# test.net
KiCad netlist of a schematic drawn in EAGLE
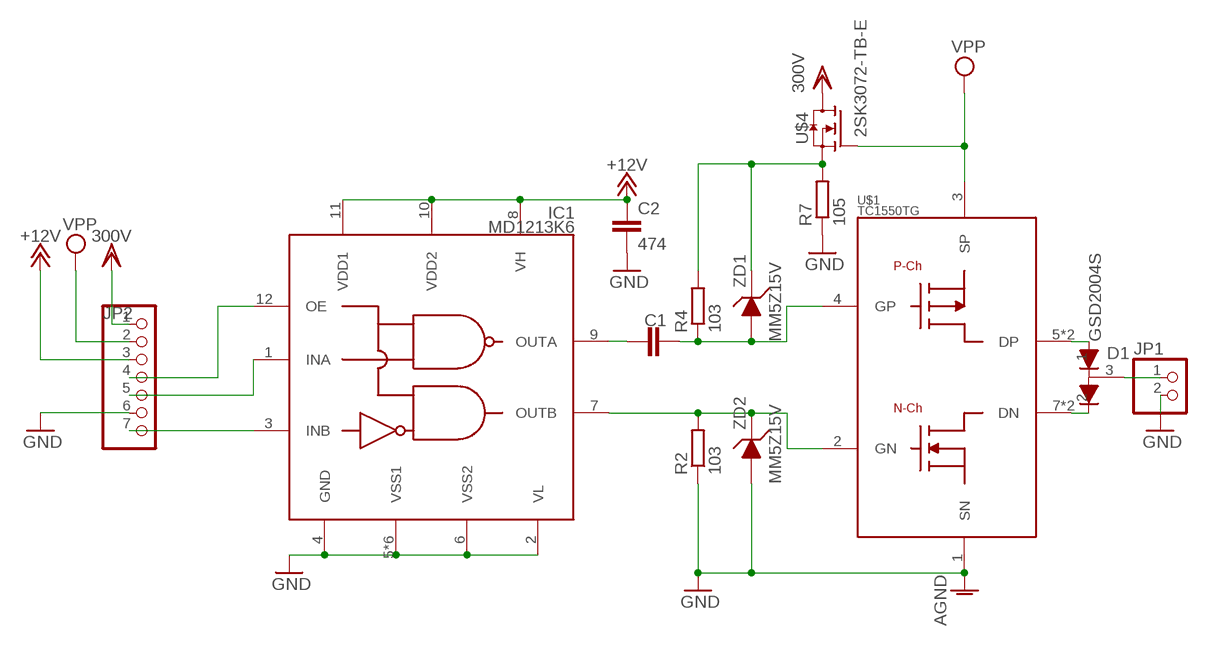
[diagram p0: schematic, sheet 1]

(export (version "E")
  (design (tool "Eeschema 10.0.6"))
  (components
    (comp (ref "C1")
      (value "C-EUC3216")
      (footprint "eagle-import:C3216")
      (libsource (lib "eagle-import") (part "C-EUC3216"))
    )
    (comp (ref "C2")
      (value "474")
      (footprint "eagle-import:C025-024X044")
      (libsource (lib "eagle-import") (part "C-EU025-024X044"))
    )
    (comp (ref "D1")
      (value "GSD2004S")
      (footprint "eagle-import:SOT23")
      (libsource (lib "eagle-import") (part "GSD2004S"))
    )
    (comp (ref "IC1")
      (value "MD1213K6")
      (footprint "eagle-import:QFN12")
      (libsource (lib "eagle-import") (part "MD1213K6"))
    )
    (comp (ref "JP1")
      (value "PINHD-1X2")
      (footprint "eagle-import:1X02")
      (libsource (lib "eagle-import") (part "PINHD-1X2"))
    )
    (comp (ref "JP2")
      (value "PINHD-1X7")
      (footprint "eagle-import:1X07")
      (libsource (lib "eagle-import") (part "PINHD-1X7"))
    )
    (comp (ref "R2")
      (value "103")
      (footprint "eagle-import:0204_5")
      (libsource (lib "eagle-import") (part "R-EU_0204/5"))
    )
    (comp (ref "R4")
      (value "103")
      (footprint "eagle-import:0204_5")
      (libsource (lib "eagle-import") (part "R-EU_0204/5"))
    )
    (comp (ref "R7")
      (value "105")
      (footprint "eagle-import:0204_5")
      (libsource (lib "eagle-import") (part "R-EU_0204/5"))
    )
    (comp (ref "U$1")
      (value "TC1550TG")
      (footprint "eagle-import:SOIC-08LG")
      (libsource (lib "eagle-import") (part "TC1550TG"))
    )
    (comp (ref "U$4")
      (value "2SK3072-TB-E")
      (footprint "eagle-import:SOT95P250X120-3")
      (libsource (lib "eagle-import") (part "2SK3072-TB-E"))
    )
    (comp (ref "ZD1")
      (value "MM5Z15V")
      (footprint "eagle-import:SOD523")
      (libsource (lib "eagle-import") (part "MM5Z15V"))
    )
    (comp (ref "ZD2")
      (value "MM5Z15V")
      (footprint "eagle-import:SOD523")
      (libsource (lib "eagle-import") (part "MM5Z15V"))
    )
  )
  (nets
    (net (code "1") (name "+12V") (class "Default")
      (node (ref "C2") (pin "1") (pinfunction "1_1") (pintype "passive"))
      (node (ref "IC1") (pin "10") (pinfunction "VDD2_10") (pintype "bidirectional"))
      (node (ref "IC1") (pin "11") (pinfunction "VDD1_11") (pintype "bidirectional"))
      (node (ref "IC1") (pin "8") (pinfunction "VH_8") (pintype "bidirectional"))
      (node (ref "JP2") (pin "3") (pinfunction "3_3") (pintype "passive"))
    )
    (net (code "2") (name "300V") (class "Default")
      (node (ref "JP2") (pin "1") (pinfunction "1_1") (pintype "passive"))
      (node (ref "U$4") (pin "3") (pinfunction "D_3") (pintype "passive"))
    )
    (net (code "3") (name "AGND") (class "Default")
      (node (ref "C2") (pin "2") (pinfunction "2_2") (pintype "passive"))
      (node (ref "IC1") (pin "2") (pinfunction "VL_2") (pintype "bidirectional"))
      (node (ref "IC1") (pin "4") (pinfunction "GND_4") (pintype "bidirectional"))
      (node (ref "IC1") (pin "5") (pinfunction "VSS1_5") (pintype "bidirectional"))
      (node (ref "IC1") (pin "6") (pinfunction "VSS2_6") (pintype "bidirectional"))
      (node (ref "IC1") (pin "THP") (pinfunction "VSS1_THP") (pintype "bidirectional"))
      (node (ref "IC1") (pin "THV$1") (pinfunction "VSS1_THV$1") (pintype "bidirectional"))
      (node (ref "IC1") (pin "THV$2") (pinfunction "VSS1_THV$2") (pintype "bidirectional"))
      (node (ref "IC1") (pin "THV$3") (pinfunction "VSS1_THV$3") (pintype "bidirectional"))
      (node (ref "IC1") (pin "THV$4") (pinfunction "VSS1_THV$4") (pintype "bidirectional"))
      (node (ref "JP1") (pin "2") (pinfunction "2_2") (pintype "passive"))
      (node (ref "JP2") (pin "6") (pinfunction "6_6") (pintype "passive"))
      (node (ref "R2") (pin "1") (pinfunction "1_1") (pintype "passive"))
      (node (ref "R7") (pin "1") (pinfunction "1_1") (pintype "passive"))
      (node (ref "U$1") (pin "1") (pinfunction "SN_1") (pintype "bidirectional"))
      (node (ref "ZD2") (pin "P$2") (pinfunction "P$1_P$2") (pintype "passive"))
    )
    (net (code "4") (name "Net-(D1-P$1)") (class "Default")
      (node (ref "D1") (pin "1") (pinfunction "P$1_1") (pintype "passive"))
      (node (ref "U$1") (pin "5") (pinfunction "DP_5") (pintype "bidirectional"))
      (node (ref "U$1") (pin "6") (pinfunction "DP_6") (pintype "bidirectional"))
    )
    (net (code "5") (name "Net-(D1-P$2)") (class "Default")
      (node (ref "D1") (pin "2") (pinfunction "P$2_2") (pintype "passive"))
      (node (ref "U$1") (pin "7") (pinfunction "DN_7") (pintype "bidirectional"))
      (node (ref "U$1") (pin "8") (pinfunction "DN_8") (pintype "bidirectional"))
    )
    (net (code "6") (name "Net-(D1-P$3)") (class "Default")
      (node (ref "D1") (pin "3") (pinfunction "P$3_3") (pintype "passive"))
      (node (ref "JP1") (pin "1") (pinfunction "1_1") (pintype "passive"))
    )
    (net (code "7") (name "Net-(IC1-INA)") (class "Default")
      (node (ref "IC1") (pin "1") (pinfunction "INA_1") (pintype "bidirectional"))
      (node (ref "JP2") (pin "5") (pinfunction "5_5") (pintype "passive"))
    )
    (net (code "8") (name "Net-(IC1-INB)") (class "Default")
      (node (ref "IC1") (pin "3") (pinfunction "INB_3") (pintype "bidirectional"))
      (node (ref "JP2") (pin "7") (pinfunction "7_7") (pintype "passive"))
    )
    (net (code "9") (name "Net-(IC1-OE)") (class "Default")
      (node (ref "IC1") (pin "12") (pinfunction "OE_12") (pintype "bidirectional"))
      (node (ref "JP2") (pin "4") (pinfunction "4_4") (pintype "passive"))
    )
    (net (code "10") (name "Net-(IC1-OUTA)") (class "Default")
      (node (ref "C1") (pin "1") (pinfunction "1_1") (pintype "passive"))
      (node (ref "IC1") (pin "9") (pinfunction "OUTA_9") (pintype "bidirectional"))
    )
    (net (code "11") (name "Net-(IC1-OUTB)") (class "Default")
      (node (ref "IC1") (pin "7") (pinfunction "OUTB_7") (pintype "bidirectional"))
      (node (ref "R2") (pin "2") (pinfunction "2_2") (pintype "passive"))
      (node (ref "U$1") (pin "2") (pinfunction "GN_2") (pintype "bidirectional"))
      (node (ref "ZD2") (pin "P$1") (pinfunction "K_P$1") (pintype "passive"))
    )
    (net (code "12") (name "Net-(U$1-GP)") (class "Default")
      (node (ref "C1") (pin "2") (pinfunction "2_2") (pintype "passive"))
      (node (ref "R4") (pin "1") (pinfunction "1_1") (pintype "passive"))
      (node (ref "U$1") (pin "4") (pinfunction "GP_4") (pintype "bidirectional"))
      (node (ref "ZD1") (pin "P$2") (pinfunction "P$1_P$2") (pintype "passive"))
    )
    (net (code "13") (name "Net-(U$4-S)") (class "Default")
      (node (ref "R4") (pin "2") (pinfunction "2_2") (pintype "passive"))
      (node (ref "R7") (pin "2") (pinfunction "2_2") (pintype "passive"))
      (node (ref "U$4") (pin "2") (pinfunction "S_2") (pintype "passive"))
      (node (ref "ZD1") (pin "P$1") (pinfunction "K_P$1") (pintype "passive"))
    )
    (net (code "14") (name "VPP") (class "Default")
      (node (ref "JP2") (pin "2") (pinfunction "2_2") (pintype "passive"))
      (node (ref "U$1") (pin "3") (pinfunction "SP_3") (pintype "bidirectional"))
      (node (ref "U$4") (pin "1") (pinfunction "G_1") (pintype "passive"))
    )
  )
)
